# 555-Sawtooth-VCO.net
KiCad netlist of a schematic drawn in EAGLE
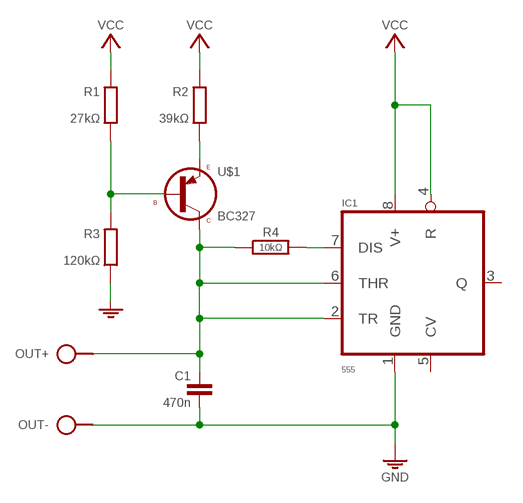
[diagram p0: schematic, sheet 1]

(export (version "E")
  (design (tool "Eeschema 10.0.6"))
  (components
    (comp (ref "C1")
      (value "470n")
      (footprint "eagle-import:C075-020X044_V")
      (libsource (lib "eagle-import") (part "C075-020X044/V"))
    )
    (comp (ref "IC1")
      (value "555")
      (footprint "eagle-import:DIL08")
      (libsource (lib "eagle-import") (part "555_ALT"))
    )
    (comp (ref "OUT")
      (value "SPAD+--+")
      (footprint "eagle-import:SPAD-+")
      (libsource (lib "eagle-import") (part "SPAD+--+"))
    )
    (comp (ref "R1")
      (value "27kΩ")
      (footprint "eagle-import:0207_10")
      (libsource (lib "eagle-import") (part "R0207/10"))
    )
    (comp (ref "R2")
      (value "39kΩ")
      (footprint "eagle-import:0207_10")
      (libsource (lib "eagle-import") (part "R0207/10"))
    )
    (comp (ref "R3")
      (value "120kΩ")
      (footprint "eagle-import:0207_10")
      (libsource (lib "eagle-import") (part "R0207/10"))
    )
    (comp (ref "R4")
      (value "10kΩ")
      (footprint "eagle-import:0204_10")
      (libsource (lib "eagle-import") (part "R-H0204/10"))
    )
    (comp (ref "S1")
      (value "VCC_GNDPWR-R")
      (footprint "eagle-import:PWR-R")
      (libsource (lib "eagle-import") (part "VCC_GNDPWR-R"))
    )
    (comp (ref "U$1")
      (value "BC327")
      (footprint "eagle-import:TO92")
      (libsource (lib "eagle-import") (part "BC327"))
    )
  )
  (nets
    (net (code "1") (name "GND") (class "Default")
      (node (ref "C1") (pin "2") (pinfunction "2_2") (pintype "passive"))
      (node (ref "IC1") (pin "1") (pinfunction "GND_1") (pintype "power_in"))
      (node (ref "OUT") (pin "1") (pinfunction "P$1_1") (pintype "passive"))
      (node (ref "R3") (pin "2") (pinfunction "1_2") (pintype "passive"))
      (node (ref "S1") (pin "1") (pinfunction "GND_1") (pintype "power_in"))
    )
    (net (code "2") (name "Net-(IC1-DIS)") (class "Default")
      (node (ref "IC1") (pin "7") (pinfunction "DIS_7") (pintype "passive"))
      (node (ref "R4") (pin "2") (pinfunction "2_2") (pintype "passive"))
    )
    (net (code "3") (name "Net-(IC1-THR)") (class "Default")
      (node (ref "C1") (pin "1") (pinfunction "1_1") (pintype "passive"))
      (node (ref "IC1") (pin "2") (pinfunction "TR_2") (pintype "input"))
      (node (ref "IC1") (pin "6") (pinfunction "THR_6") (pintype "input"))
      (node (ref "OUT") (pin "2") (pinfunction "P$1_2") (pintype "passive"))
      (node (ref "R4") (pin "1") (pinfunction "1_1") (pintype "passive"))
      (node (ref "U$1") (pin "1") (pinfunction "C_1") (pintype "passive"))
    )
    (net (code "4") (name "Net-(R1-1)") (class "Default")
      (node (ref "R1") (pin "2") (pinfunction "1_2") (pintype "passive"))
      (node (ref "R3") (pin "1") (pinfunction "2_1") (pintype "passive"))
      (node (ref "U$1") (pin "2") (pinfunction "B_2") (pintype "passive"))
    )
    (net (code "5") (name "Net-(R2-1)") (class "Default")
      (node (ref "R2") (pin "2") (pinfunction "1_2") (pintype "passive"))
      (node (ref "U$1") (pin "3") (pinfunction "E_3") (pintype "passive"))
    )
    (net (code "6") (name "VCC") (class "Default")
      (node (ref "IC1") (pin "4") (pinfunction "R_4") (pintype "input"))
      (node (ref "IC1") (pin "8") (pinfunction "V+_8") (pintype "power_in"))
      (node (ref "R1") (pin "1") (pinfunction "2_1") (pintype "passive"))
      (node (ref "R2") (pin "1") (pinfunction "2_1") (pintype "passive"))
      (node (ref "S1") (pin "2") (pinfunction "VCC_2") (pintype "power_in"))
    )
    (net (code "7") (name "unconnected-(IC1-CV-Pad5)") (class "Default")
      (node (ref "IC1") (pin "5") (pinfunction "CV_5") (pintype "input"))
    )
    (net (code "8") (name "unconnected-(IC1-Q-Pad3)") (class "Default")
      (node (ref "IC1") (pin "3") (pinfunction "Q_3") (pintype "output"))
    )
  )
)
